# AMU-S15-V00-BSPDSystem.net
KiCad netlist of a schematic drawn in Altium Designer
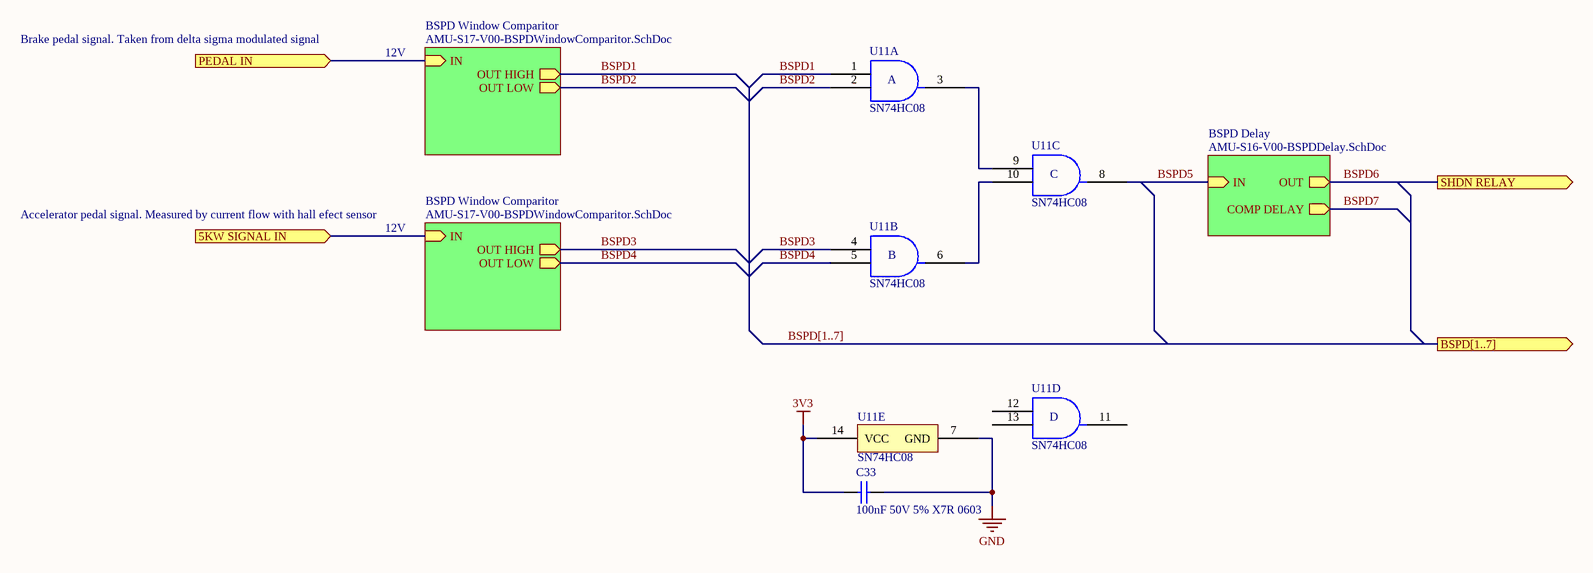
[diagram p0: AMU-S15-V00-BSPDSystem.SchDoc]

(export (version "E")
  (design (tool "Eeschema 10.0.6"))
  (components
    (comp (ref "C33")
      (value "100nF 50V 5% X7R 0603")
      (footprint "Cap_Ceramic_0603")
      (description "Capacitor, Ceramic, SMD, 100nF, 50V, 5%, X7R, 0603")
      (libsource (lib "StandardCapacitors") (part "100nF 50V 5% X7R 0603"))
    )
    (comp (ref "U11")
      (value "SN74HC08")
      (footprint "TSSOP-14")
      (description "Quadruple 2-Input Positive-AND Gates")
      (libsource (lib "QUTMS_OpAmpLibrary") (part "SN74HC08"))
    )
  )
  (nets
    (net (code "2") (name "/BSPD1") (class "Default")
      (node (ref "U11") (pin "1") (pinfunction "1A_1") (pintype "passive"))
    )
    (net (code "3") (name "/BSPD2") (class "Default")
      (node (ref "U11") (pin "2") (pinfunction "1B_2") (pintype "passive"))
    )
    (net (code "4") (name "/BSPD3") (class "Default")
      (node (ref "U11") (pin "4") (pinfunction "2A_4") (pintype "passive"))
    )
    (net (code "5") (name "/BSPD4") (class "Default")
      (node (ref "U11") (pin "5") (pinfunction "2B_5") (pintype "passive"))
    )
    (net (code "6") (name "/BSPD5") (class "Default")
      (node (ref "U11") (pin "8") (pinfunction "3Y_8") (pintype "passive"))
    )
    (net (code "11") (name "3V3") (class "Default")
      (node (ref "C33") (pin "2") (pinfunction "2_2") (pintype "passive"))
      (node (ref "U11") (pin "14") (pinfunction "VCC_14") (pintype "passive"))
    )
    (net (code "12") (name "GND") (class "Default")
      (node (ref "C33") (pin "1") (pinfunction "1_1") (pintype "passive"))
      (node (ref "U11") (pin "7") (pinfunction "GND_7") (pintype "passive"))
    )
    (net (code "13") (name "Net-(U11A-1Y)") (class "Default")
      (node (ref "U11") (pin "3") (pinfunction "1Y_3") (pintype "passive"))
      (node (ref "U11") (pin "9") (pinfunction "3A_9") (pintype "passive"))
    )
    (net (code "14") (name "Net-(U11B-2Y)") (class "Default")
      (node (ref "U11") (pin "10") (pinfunction "3B_10") (pintype "passive"))
      (node (ref "U11") (pin "6") (pinfunction "2Y_6") (pintype "passive"))
    )
    (net (code "15") (name "unconnected-(U11D-4A-Pad12)") (class "Default")
      (node (ref "U11") (pin "12") (pinfunction "4A_12") (pintype "passive"))
    )
    (net (code "16") (name "unconnected-(U11D-4B-Pad13)") (class "Default")
      (node (ref "U11") (pin "13") (pinfunction "4B_13") (pintype "passive"))
    )
    (net (code "17") (name "unconnected-(U11D-4Y-Pad11)") (class "Default")
      (node (ref "U11") (pin "11") (pinfunction "4Y_11") (pintype "passive"))
    )
  )
)
